# IEPE.net
KiCad netlist of a schematic drawn in Altium Designer
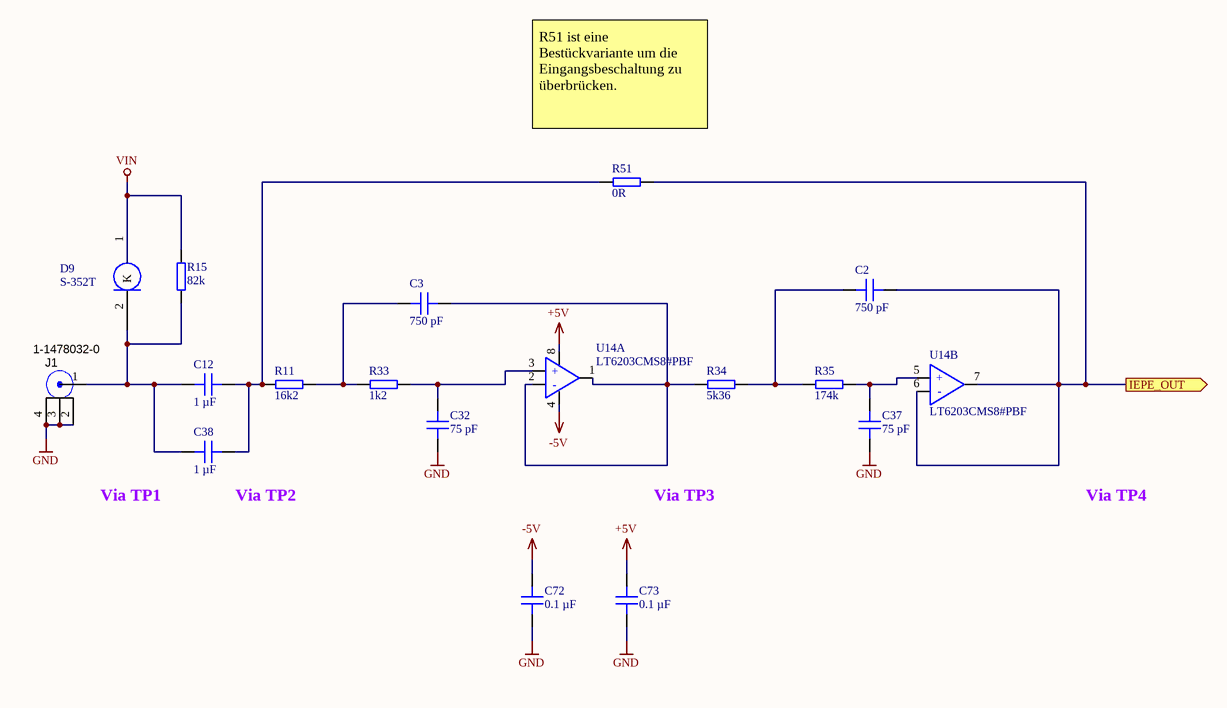
[diagram p0: IEPE.SchDoc]

(export (version "E")
  (design (tool "Eeschema 10.0.6"))
  (components
    (comp (ref "C2")
      (value "750 pF")
      (footprint "C_0603")
      (description "Capacitor 0603, 50 VDC, 750 pF, C0G")
      (fields
        (field (name "MANUFACTURER PART NUMBER") "C0603C751J5GACAUTO")
        (field (name "MANUFACTURER") "KEMET")
        (field (name "CREATED FROM") "MGremer")
      )
      (libsource (lib "user") (part "Capacitor"))
    )
    (comp (ref "C3")
      (value "750 pF")
      (footprint "C_0603")
      (description "Capacitor 0603, 50 VDC, 750 pF, C0G")
      (fields
        (field (name "MANUFACTURER PART NUMBER") "C0603C751J5GACAUTO")
        (field (name "MANUFACTURER") "KEMET")
        (field (name "CREATED FROM") "MGremer")
      )
      (libsource (lib "user") (part "Capacitor"))
    )
    (comp (ref "C12")
      (value "1 µF")
      (footprint "C_0603")
      (description "Capacitor 0603, 50 VDC, 1 µF, X7R")
      (fields
        (field (name "MANUFACTURER PART NUMBER") "UMK107AB7105KA-T")
        (field (name "MANUFACTURER") "Taiyo Yuden")
        (field (name "CREATED FROM") "MGremer")
      )
      (libsource (lib "user") (part "Capacitor"))
    )
    (comp (ref "C32")
      (value "75 pF")
      (footprint "C_0603")
      (description "Capacitor 0603, 50 VDC, 75 pF, X7R")
      (fields
        (field (name "MANUFACTURER PART NUMBER") "C0603C750J5RACAUTO")
        (field (name "MANUFACTURER") "KEMET")
        (field (name "CREATED FROM") "MGremer")
      )
      (libsource (lib "user") (part "Capacitor"))
    )
    (comp (ref "C37")
      (value "75 pF")
      (footprint "C_0603")
      (description "Capacitor 0603, 50 VDC, 75 pF, X7R")
      (fields
        (field (name "MANUFACTURER PART NUMBER") "C0603C750J5RACAUTO")
        (field (name "MANUFACTURER") "KEMET")
        (field (name "CREATED FROM") "MGremer")
      )
      (libsource (lib "user") (part "Capacitor"))
    )
    (comp (ref "C38")
      (value "1 µF")
      (footprint "C_0603")
      (description "Capacitor 0603, 50 VDC, 1 µF, X7R")
      (fields
        (field (name "MANUFACTURER PART NUMBER") "UMK107AB7105KA-T")
        (field (name "MANUFACTURER") "Taiyo Yuden")
        (field (name "CREATED FROM") "MGremer")
      )
      (libsource (lib "user") (part "Capacitor"))
    )
    (comp (ref "C72")
      (value "0.1 µF")
      (footprint "C_0603")
      (description "Capacitor 0603, 50 VDC, 0.1 µF, X7R")
      (fields
        (field (name "MANUFACTURER PART NUMBER") "C0603X104K5RAC7411")
        (field (name "MANUFACTURER") "KEMET")
        (field (name "CREATED FROM") "MGremer")
      )
      (libsource (lib "user") (part "Capacitor"))
    )
    (comp (ref "C73")
      (value "0.1 µF")
      (footprint "C_0603")
      (description "Capacitor 0603, 50 VDC, 0.1 µF, X7R")
      (fields
        (field (name "MANUFACTURER PART NUMBER") "C0603X104K5RAC7411")
        (field (name "MANUFACTURER") "KEMET")
        (field (name "CREATED FROM") "MGremer")
      )
      (libsource (lib "user") (part "Capacitor"))
    )
    (comp (ref "D9")
      (value "S-352T")
      (footprint "CRD")
      (description "Current Regulator Diodes 100V 3.5mA")
      (fields (field (name "MANUFACTURER") "Semitec") (field (name "CREATED FROM") "PTurowski"))
      (libsource (lib "user") (part "CRD"))
    )
    (comp (ref "J1")
      (value "1-1478032-0")
      (footprint "Right Angle BNC")
      (description "BNC Connector")
      (fields
        (field (name "MANUFACTURER") "TE")
        (field (name "PARTNUMBER") "Used in BOM report")
        (field (name "SYMBOLCREATOR") "Use LDAP id")
        (field (name "CREATED FROM") "FSchoenig, MGremer")
      )
      (libsource (lib "user") (part "BNC"))
    )
    (comp (ref "R11")
      (value "16k2")
      (footprint "RES 0603_1608")
      (description "SMD resistor 1%")
      (fields
        (field (name "MANUFACTURER PART NUMBER") "AC0603FR-0716K2L")
        (field (name "MANUFACTURER") "YAGEO")
        (field (name "CREATED FROM") "MGremer")
      )
      (libsource (lib "user") (part "Resistor"))
    )
    (comp (ref "R15")
      (value "82k")
      (footprint "RES 0603_1608")
      (description "SMD resistor E24 series")
      (fields
        (field (name "MANUFACTURER PART NUMBER") "RK73B1JTTDD823J")
        (field (name "MANUFACTURER") "KOA Speer")
        (field (name "CREATED FROM") "MGremer")
      )
      (libsource (lib "user") (part "Resistor"))
    )
    (comp (ref "R33")
      (value "1k2")
      (footprint "RES 0603_1608")
      (description "SMD resistor E24 series")
      (fields
        (field (name "MANUFACTURER PART NUMBER") "RK73B1JTTD122J")
        (field (name "MANUFACTURER") "KOA Speer")
        (field (name "CREATED FROM") "MGremer")
      )
      (libsource (lib "user") (part "Resistor"))
    )
    (comp (ref "R34")
      (value "5k36")
      (footprint "RES 0603_1608")
      (description "SMD resistor 1%")
      (fields
        (field (name "MANUFACTURER PART NUMBER") "AC0603FR-075K36L")
        (field (name "MANUFACTURER") "YAGEO")
        (field (name "CREATED FROM") "MGremer")
      )
      (libsource (lib "user") (part "Resistor"))
    )
    (comp (ref "R35")
      (value "174k")
      (footprint "RES 0603_1608")
      (description "SMD resistor 1%")
      (fields
        (field (name "MANUFACTURER PART NUMBER") "RC0603FR-07174KL")
        (field (name "MANUFACTURER") "YAGEO")
        (field (name "CREATED FROM") "MGremer")
      )
      (libsource (lib "user") (part "Resistor"))
    )
    (comp (ref "R51")
      (value "0R")
      (footprint "RES 0603_1608")
      (description "SMD resistor E24 series")
      (fields
        (field (name "MANUFACTURER PART NUMBER") "RC0603JR-070RL")
        (field (name "MANUFACTURER") "YAGEO")
        (field (name "CREATED FROM") "MGremer")
      )
      (libsource (lib "user") (part "Resistor"))
    )
    (comp (ref "U14")
      (value "LT6203CMS8#PBF")
      (footprint "MSOP8_3x3-8N")
      (description "Operational Amplifier, Rail-to-Rail, ultralow noise")
      (fields (field (name "MANUFACTURER") "Analog Devices") (field (name "CREATED FROM") "MGremer"))
      (libsource (lib "user") (part "LT6203_MSOP8"))
    )
  )
  (nets
    (net (code "1") (name "+5V") (class "Default")
      (node (ref "C73") (pin "2") (pinfunction "2_2") (pintype "passive"))
      (node (ref "U14") (pin "8") (pintype "passive"))
    )
    (net (code "2") (name "-5V") (class "Default")
      (node (ref "C72") (pin "2") (pinfunction "2_2") (pintype "passive"))
      (node (ref "U14") (pin "4") (pintype "passive"))
    )
    (net (code "3") (name "/IEPE_OUT") (class "Default")
      (node (ref "C2") (pin "2") (pinfunction "2_2") (pintype "passive"))
      (node (ref "R51") (pin "2") (pinfunction "2_2") (pintype "passive"))
      (node (ref "U14") (pin "6") (pinfunction "-_6") (pintype "passive"))
      (node (ref "U14") (pin "7") (pintype "passive"))
    )
    (net (code "4") (name "GND") (class "Default")
      (node (ref "C32") (pin "1") (pinfunction "1_1") (pintype "passive"))
      (node (ref "C37") (pin "1") (pinfunction "1_1") (pintype "passive"))
      (node (ref "C72") (pin "1") (pinfunction "1_1") (pintype "passive"))
      (node (ref "C73") (pin "1") (pinfunction "1_1") (pintype "passive"))
      (node (ref "J1") (pin "2") (pinfunction "2_2") (pintype "passive"))
      (node (ref "J1") (pin "3") (pinfunction "3_3") (pintype "passive"))
      (node (ref "J1") (pin "4") (pinfunction "4_4") (pintype "passive"))
    )
    (net (code "5") (name "Net-(C2-Pad1)") (class "Default")
      (node (ref "C2") (pin "1") (pinfunction "1_1") (pintype "passive"))
      (node (ref "R34") (pin "2") (pinfunction "2_2") (pintype "passive"))
      (node (ref "R35") (pin "1") (pinfunction "1_1") (pintype "passive"))
    )
    (net (code "6") (name "Net-(C3-Pad1)") (class "Default")
      (node (ref "C3") (pin "1") (pinfunction "1_1") (pintype "passive"))
      (node (ref "R11") (pin "2") (pinfunction "2_2") (pintype "passive"))
      (node (ref "R33") (pin "1") (pinfunction "1_1") (pintype "passive"))
    )
    (net (code "7") (name "Net-(C12-Pad2)") (class "Default")
      (node (ref "C12") (pin "2") (pinfunction "2_2") (pintype "passive"))
      (node (ref "C38") (pin "2") (pinfunction "2_2") (pintype "passive"))
      (node (ref "R11") (pin "1") (pinfunction "1_1") (pintype "passive"))
      (node (ref "R51") (pin "1") (pinfunction "1_1") (pintype "passive"))
    )
    (net (code "8") (name "Net-(D9-K)") (class "Default")
      (node (ref "C12") (pin "1") (pinfunction "1_1") (pintype "passive"))
      (node (ref "C38") (pin "1") (pinfunction "1_1") (pintype "passive"))
      (node (ref "D9") (pin "2") (pinfunction "K_2") (pintype "passive"))
      (node (ref "J1") (pin "1") (pinfunction "1_1") (pintype "passive"))
      (node (ref "R15") (pin "1") (pinfunction "1_1") (pintype "passive"))
    )
    (net (code "9") (name "Net-(U14A-+)") (class "Default")
      (node (ref "C32") (pin "2") (pinfunction "2_2") (pintype "passive"))
      (node (ref "R33") (pin "2") (pinfunction "2_2") (pintype "passive"))
      (node (ref "U14") (pin "3") (pinfunction "+_3") (pintype "passive"))
    )
    (net (code "10") (name "Net-(U14A--)") (class "Default")
      (node (ref "C3") (pin "2") (pinfunction "2_2") (pintype "passive"))
      (node (ref "R34") (pin "1") (pinfunction "1_1") (pintype "passive"))
      (node (ref "U14") (pin "1") (pintype "passive"))
      (node (ref "U14") (pin "2") (pinfunction "-_2") (pintype "passive"))
    )
    (net (code "11") (name "Net-(U14B-+)") (class "Default")
      (node (ref "C37") (pin "2") (pinfunction "2_2") (pintype "passive"))
      (node (ref "R35") (pin "2") (pinfunction "2_2") (pintype "passive"))
      (node (ref "U14") (pin "5") (pinfunction "+_5") (pintype "passive"))
    )
    (net (code "12") (name "VIN") (class "Default")
      (node (ref "D9") (pin "1") (pinfunction "A_1") (pintype "passive"))
      (node (ref "R15") (pin "2") (pinfunction "2_2") (pintype "passive"))
    )
  )
)
